# expansion_module_audio_line_out.net
KiCad netlist of a schematic drawn in EAGLE
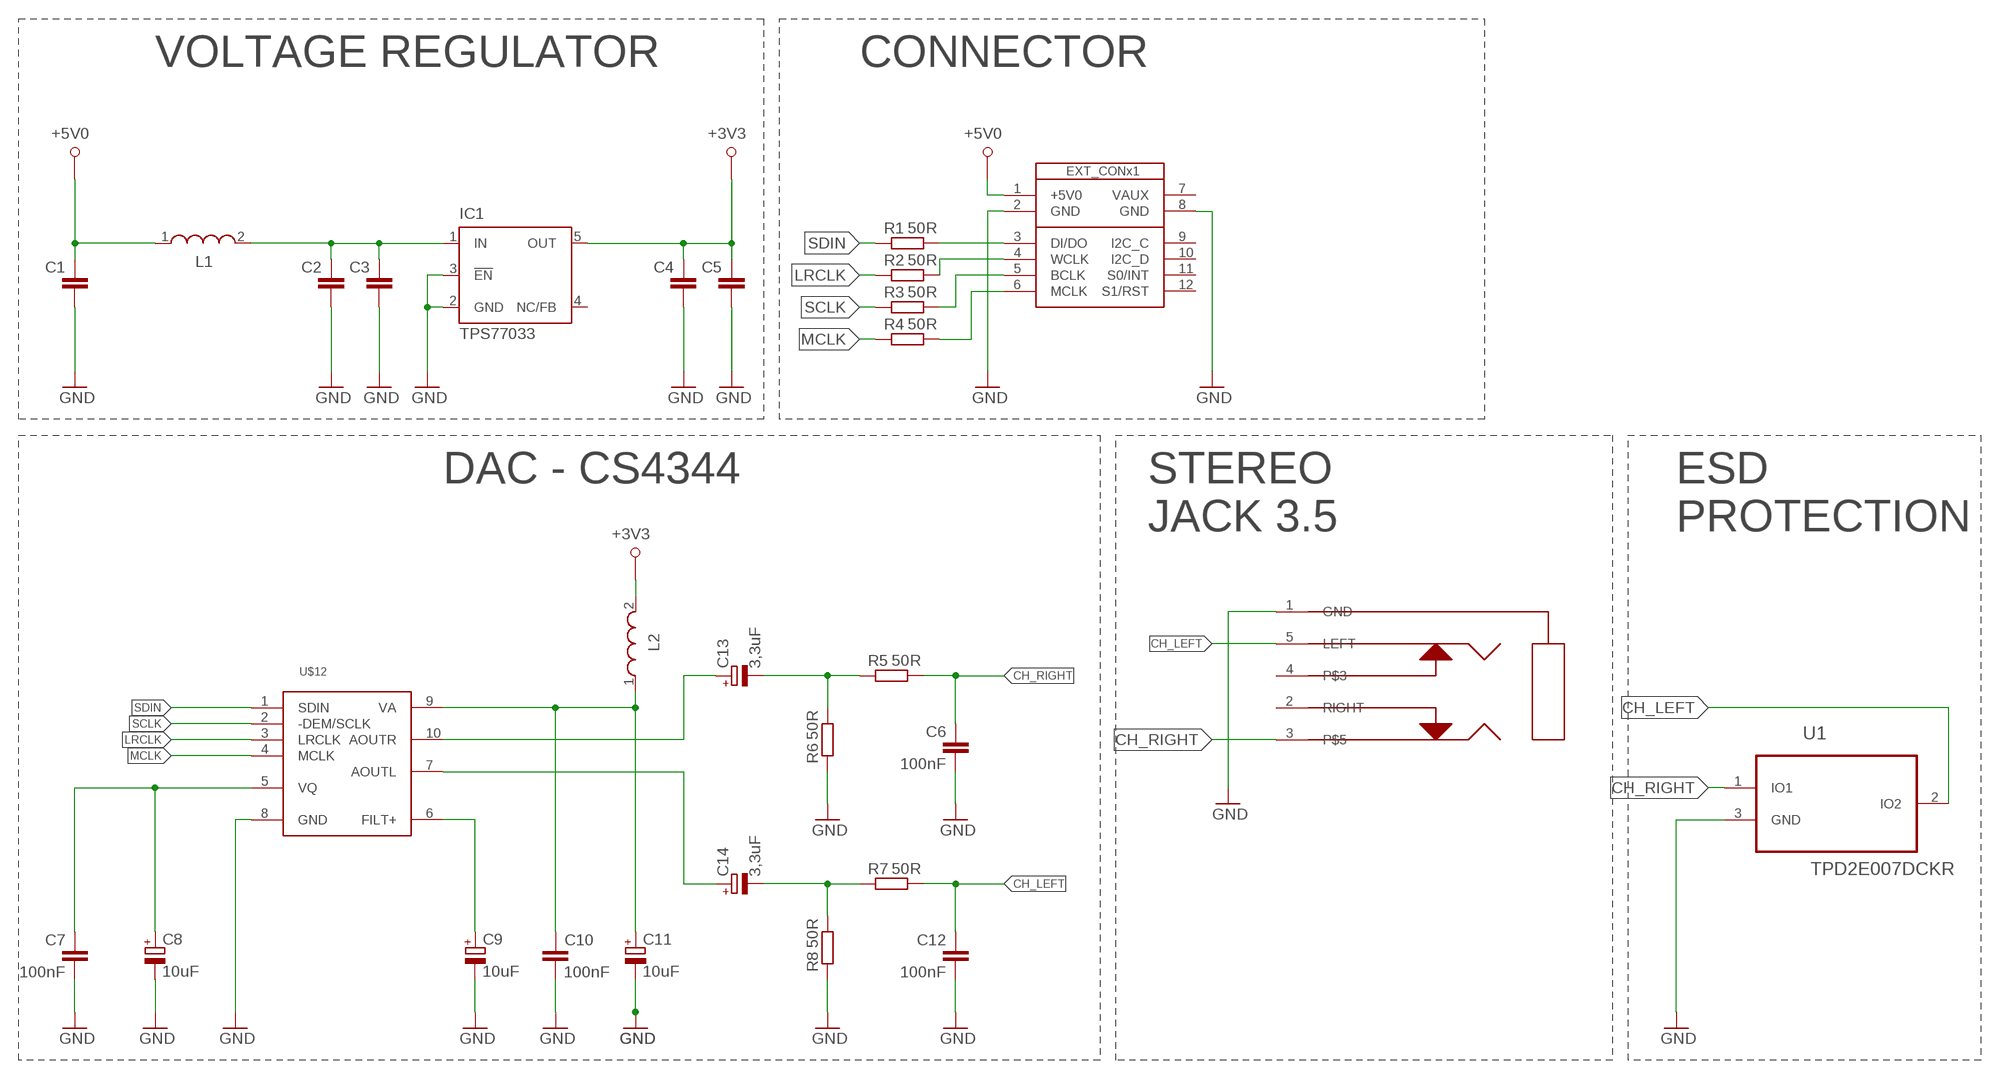
[diagram p0: schematic, sheet 1]

(export (version "E")
  (design (tool "Eeschema 10.0.6"))
  (components
    (comp (ref "C1")
      (value "C-EUC0805")
      (footprint "eagle-import:C0805")
      (libsource (lib "eagle-import") (part "C-EUC0805"))
    )
    (comp (ref "C2")
      (value "C-EUC0805")
      (footprint "eagle-import:C0805")
      (libsource (lib "eagle-import") (part "C-EUC0805"))
    )
    (comp (ref "C3")
      (value "C-EUC0805")
      (footprint "eagle-import:C0805")
      (libsource (lib "eagle-import") (part "C-EUC0805"))
    )
    (comp (ref "C4")
      (value "C-EUC0805")
      (footprint "eagle-import:C0805")
      (libsource (lib "eagle-import") (part "C-EUC0805"))
    )
    (comp (ref "C5")
      (value "C-EUC0805")
      (footprint "eagle-import:C0805")
      (libsource (lib "eagle-import") (part "C-EUC0805"))
    )
    (comp (ref "C6")
      (value "100nF")
      (footprint "eagle-import:C0805")
      (libsource (lib "eagle-import") (part "C-EUC0805"))
    )
    (comp (ref "C7")
      (value "100nF")
      (footprint "eagle-import:C0805")
      (libsource (lib "eagle-import") (part "C-EUC0805"))
    )
    (comp (ref "C8")
      (value "10uF")
      (footprint "eagle-import:SMC_A")
      (libsource (lib "eagle-import") (part "CPOL-EUSMCA"))
    )
    (comp (ref "C9")
      (value "10uF")
      (footprint "eagle-import:SMC_A")
      (libsource (lib "eagle-import") (part "CPOL-EUSMCA"))
    )
    (comp (ref "C10")
      (value "100nF")
      (footprint "eagle-import:C0805")
      (libsource (lib "eagle-import") (part "C-EUC0805"))
    )
    (comp (ref "C11")
      (value "10uF")
      (footprint "eagle-import:SMC_A")
      (libsource (lib "eagle-import") (part "CPOL-EUSMCA"))
    )
    (comp (ref "C12")
      (value "100nF")
      (footprint "eagle-import:C0805")
      (libsource (lib "eagle-import") (part "C-EUC0805"))
    )
    (comp (ref "C13")
      (value "3,3uF")
      (footprint "eagle-import:SMC_A")
      (libsource (lib "eagle-import") (part "CPOL-EUSMCA"))
    )
    (comp (ref "C14")
      (value "3,3uF")
      (footprint "eagle-import:SMC_A")
      (libsource (lib "eagle-import") (part "CPOL-EUSMCA"))
    )
    (comp (ref "IC1")
      (value "TPS77033")
      (footprint "eagle-import:SOT23-DBV")
      (fields (field (name "MF") "TEXAS INSTRUMENTS") (field (name "MPN") "TPS77033DBVT"))
      (libsource (lib "eagle-import") (part "TPS77033"))
    )
    (comp (ref "L1")
      (value "WE-LQ_1210")
      (footprint "eagle-import:WE-LQ_M")
      (libsource (lib "eagle-import") (part "WE-LQ_1210"))
    )
    (comp (ref "L2")
      (value "WE-LQ_1210")
      (footprint "eagle-import:WE-LQ_M")
      (libsource (lib "eagle-import") (part "WE-LQ_1210"))
    )
    (comp (ref "R1")
      (value "50R")
      (footprint "eagle-import:R0805")
      (libsource (lib "eagle-import") (part "R-EU_R0805"))
    )
    (comp (ref "R2")
      (value "50R")
      (footprint "eagle-import:R0805")
      (libsource (lib "eagle-import") (part "R-EU_R0805"))
    )
    (comp (ref "R3")
      (value "50R")
      (footprint "eagle-import:R0805")
      (libsource (lib "eagle-import") (part "R-EU_R0805"))
    )
    (comp (ref "R4")
      (value "50R")
      (footprint "eagle-import:R0805")
      (libsource (lib "eagle-import") (part "R-EU_R0805"))
    )
    (comp (ref "R5")
      (value "50R")
      (footprint "eagle-import:R0805")
      (libsource (lib "eagle-import") (part "R-EU_R0805"))
    )
    (comp (ref "R6")
      (value "50R")
      (footprint "eagle-import:R0805")
      (libsource (lib "eagle-import") (part "R-EU_R0805"))
    )
    (comp (ref "R7")
      (value "50R")
      (footprint "eagle-import:R0805")
      (libsource (lib "eagle-import") (part "R-EU_R0805"))
    )
    (comp (ref "R8")
      (value "50R")
      (footprint "eagle-import:R0805")
      (libsource (lib "eagle-import") (part "R-EU_R0805"))
    )
    (comp (ref "U$1")
      (value "SB_EXT_CON_X1_I2S")
      (footprint "eagle-import:SB_EXT_CON_X1_FULL")
      (libsource (lib "eagle-import") (part "SB_EXT_CON_X1_I2S"))
    )
    (comp (ref "U$12")
      (value "CS4344")
      (footprint "eagle-import:MSOP10")
      (libsource (lib "eagle-import") (part "CS4344"))
    )
    (comp (ref "U$27")
      (value "JACK_STEREO_5_PIN")
      (footprint "eagle-import:JACK_STEREO_5_PIN")
      (libsource (lib "eagle-import") (part "JACK_STEREO_5_PIN"))
    )
    (comp (ref "U1")
      (value "TPD2E007DCKR")
      (footprint "eagle-import:SOT65P210X110-3N")
      (libsource (lib "eagle-import") (part "TPD2E007DCKR"))
    )
  )
  (nets
    (net (code "1") (name "+3V3") (class "Default")
      (node (ref "C4") (pin "2") (pinfunction "2_2") (pintype "passive"))
      (node (ref "C5") (pin "2") (pinfunction "2_2") (pintype "passive"))
      (node (ref "IC1") (pin "5") (pinfunction "OUT_5") (pintype "passive"))
      (node (ref "L2") (pin "2") (pinfunction "2_2") (pintype "passive"))
    )
    (net (code "2") (name "+5V0") (class "Default")
      (node (ref "C1") (pin "2") (pinfunction "2_2") (pintype "passive"))
      (node (ref "L1") (pin "1") (pinfunction "1_1") (pintype "passive"))
      (node (ref "U$1") (pin "1") (pinfunction "+5V0_1") (pintype "bidirectional"))
    )
    (net (code "3") (name "CH_LEFT") (class "Default")
      (node (ref "C12") (pin "2") (pinfunction "2_2") (pintype "passive"))
      (node (ref "R7") (pin "2") (pinfunction "2_2") (pintype "passive"))
      (node (ref "U$27") (pin "5") (pinfunction "LEFT_5") (pintype "bidirectional"))
      (node (ref "U1") (pin "2") (pinfunction "IO2_2") (pintype "bidirectional"))
    )
    (net (code "4") (name "CH_RIGHT") (class "Default")
      (node (ref "C6") (pin "2") (pinfunction "2_2") (pintype "passive"))
      (node (ref "R5") (pin "2") (pinfunction "2_2") (pintype "passive"))
      (node (ref "U$27") (pin "3") (pinfunction "P$5_3") (pintype "bidirectional"))
      (node (ref "U1") (pin "1") (pinfunction "IO1_1") (pintype "bidirectional"))
    )
    (net (code "5") (name "GND") (class "Default")
      (node (ref "C1") (pin "1") (pinfunction "1_1") (pintype "passive"))
      (node (ref "C10") (pin "1") (pinfunction "1_1") (pintype "passive"))
      (node (ref "C11") (pin "-") (pinfunction "-_-") (pintype "passive"))
      (node (ref "C12") (pin "1") (pinfunction "1_1") (pintype "passive"))
      (node (ref "C2") (pin "1") (pinfunction "1_1") (pintype "passive"))
      (node (ref "C3") (pin "1") (pinfunction "1_1") (pintype "passive"))
      (node (ref "C4") (pin "1") (pinfunction "1_1") (pintype "passive"))
      (node (ref "C5") (pin "1") (pinfunction "1_1") (pintype "passive"))
      (node (ref "C6") (pin "1") (pinfunction "1_1") (pintype "passive"))
      (node (ref "C7") (pin "1") (pinfunction "1_1") (pintype "passive"))
      (node (ref "C8") (pin "-") (pinfunction "-_-") (pintype "passive"))
      (node (ref "C9") (pin "-") (pinfunction "-_-") (pintype "passive"))
      (node (ref "IC1") (pin "2") (pinfunction "GND_2") (pintype "power_in"))
      (node (ref "IC1") (pin "3") (pinfunction "~{EN}_3") (pintype "input"))
      (node (ref "R6") (pin "1") (pinfunction "1_1") (pintype "passive"))
      (node (ref "R8") (pin "1") (pinfunction "1_1") (pintype "passive"))
      (node (ref "U$1") (pin "2") (pinfunction "GND_2") (pintype "bidirectional"))
      (node (ref "U$1") (pin "8") (pinfunction "GND_8") (pintype "bidirectional"))
      (node (ref "U$12") (pin "8") (pinfunction "GND_8") (pintype "power_in"))
      (node (ref "U$27") (pin "1") (pinfunction "GND_1") (pintype "bidirectional"))
      (node (ref "U1") (pin "3") (pinfunction "GND_3") (pintype "passive"))
    )
    (net (code "6") (name "LRCLK") (class "Default")
      (node (ref "R2") (pin "1") (pinfunction "1_1") (pintype "passive"))
      (node (ref "U$12") (pin "3") (pinfunction "LRCLK_3") (pintype "input"))
    )
    (net (code "7") (name "MCLK") (class "Default")
      (node (ref "R4") (pin "1") (pinfunction "1_1") (pintype "passive"))
      (node (ref "U$12") (pin "4") (pinfunction "MCLK_4") (pintype "input"))
    )
    (net (code "8") (name "Net-(C13-Pad-)") (class "Default")
      (node (ref "C13") (pin "-") (pinfunction "-_-") (pintype "passive"))
      (node (ref "R5") (pin "1") (pinfunction "1_1") (pintype "passive"))
      (node (ref "R6") (pin "2") (pinfunction "2_2") (pintype "passive"))
    )
    (net (code "9") (name "Net-(C14-Pad-)") (class "Default")
      (node (ref "C14") (pin "-") (pinfunction "-_-") (pintype "passive"))
      (node (ref "R7") (pin "1") (pinfunction "1_1") (pintype "passive"))
      (node (ref "R8") (pin "2") (pinfunction "2_2") (pintype "passive"))
    )
    (net (code "10") (name "Net-(IC1-IN)") (class "Default")
      (node (ref "C2") (pin "2") (pinfunction "2_2") (pintype "passive"))
      (node (ref "C3") (pin "2") (pinfunction "2_2") (pintype "passive"))
      (node (ref "IC1") (pin "1") (pinfunction "IN_1") (pintype "input"))
      (node (ref "L1") (pin "2") (pinfunction "2_2") (pintype "passive"))
    )
    (net (code "11") (name "Net-(U$1-BCLK)") (class "Default")
      (node (ref "R3") (pin "2") (pinfunction "2_2") (pintype "passive"))
      (node (ref "U$1") (pin "5") (pinfunction "BCLK_5") (pintype "bidirectional"))
    )
    (net (code "12") (name "Net-(U$1-DI{slash}DO)") (class "Default")
      (node (ref "R1") (pin "2") (pinfunction "2_2") (pintype "passive"))
      (node (ref "U$1") (pin "3") (pinfunction "DI/DO_3") (pintype "bidirectional"))
    )
    (net (code "13") (name "Net-(U$1-MCLK)") (class "Default")
      (node (ref "R4") (pin "2") (pinfunction "2_2") (pintype "passive"))
      (node (ref "U$1") (pin "6") (pinfunction "MCLK_6") (pintype "bidirectional"))
    )
    (net (code "14") (name "Net-(U$1-WCLK)") (class "Default")
      (node (ref "R2") (pin "2") (pinfunction "2_2") (pintype "passive"))
      (node (ref "U$1") (pin "4") (pinfunction "WCLK_4") (pintype "bidirectional"))
    )
    (net (code "15") (name "Net-(U$12-AOUTL)") (class "Default")
      (node (ref "C14") (pin "+") (pinfunction "+_+") (pintype "passive"))
      (node (ref "U$12") (pin "7") (pinfunction "AOUTL_7") (pintype "output"))
    )
    (net (code "16") (name "Net-(U$12-AOUTR)") (class "Default")
      (node (ref "C13") (pin "+") (pinfunction "+_+") (pintype "passive"))
      (node (ref "U$12") (pin "10") (pinfunction "AOUTR_10") (pintype "output"))
    )
    (net (code "17") (name "Net-(U$12-FILT+)") (class "Default")
      (node (ref "C9") (pin "+") (pinfunction "+_+") (pintype "passive"))
      (node (ref "U$12") (pin "6") (pinfunction "FILT+_6") (pintype "passive"))
    )
    (net (code "18") (name "Net-(U$12-VA)") (class "Default")
      (node (ref "C10") (pin "2") (pinfunction "2_2") (pintype "passive"))
      (node (ref "C11") (pin "+") (pinfunction "+_+") (pintype "passive"))
      (node (ref "L2") (pin "1") (pinfunction "1_1") (pintype "passive"))
      (node (ref "U$12") (pin "9") (pinfunction "VA_9") (pintype "power_in"))
    )
    (net (code "19") (name "Net-(U$12-VQ)") (class "Default")
      (node (ref "C7") (pin "2") (pinfunction "2_2") (pintype "passive"))
      (node (ref "C8") (pin "+") (pinfunction "+_+") (pintype "passive"))
      (node (ref "U$12") (pin "5") (pinfunction "VQ_5") (pintype "passive"))
    )
    (net (code "20") (name "SCLK") (class "Default")
      (node (ref "R3") (pin "1") (pinfunction "1_1") (pintype "passive"))
      (node (ref "U$12") (pin "2") (pinfunction "-DEM/SCLK_2") (pintype "input"))
    )
    (net (code "21") (name "SDIN") (class "Default")
      (node (ref "R1") (pin "1") (pinfunction "1_1") (pintype "passive"))
      (node (ref "U$12") (pin "1") (pinfunction "SDIN_1") (pintype "input"))
    )
    (net (code "22") (name "unconnected-(IC1-NC{slash}FB-Pad4)") (class "Default")
      (node (ref "IC1") (pin "4") (pinfunction "NC/FB_4") (pintype "passive"))
    )
    (net (code "23") (name "unconnected-(U$1-I2C_C-Pad9)") (class "Default")
      (node (ref "U$1") (pin "9") (pinfunction "I2C_C_9") (pintype "bidirectional"))
    )
    (net (code "24") (name "unconnected-(U$1-I2C_D-Pad10)") (class "Default")
      (node (ref "U$1") (pin "10") (pinfunction "I2C_D_10") (pintype "bidirectional"))
    )
    (net (code "25") (name "unconnected-(U$1-S0{slash}INT-Pad11)") (class "Default")
      (node (ref "U$1") (pin "11") (pinfunction "S0/INT_11") (pintype "bidirectional"))
    )
    (net (code "26") (name "unconnected-(U$1-S1{slash}RST-Pad12)") (class "Default")
      (node (ref "U$1") (pin "12") (pinfunction "S1/RST_12") (pintype "bidirectional"))
    )
    (net (code "27") (name "unconnected-(U$1-VAUX-Pad7)") (class "Default")
      (node (ref "U$1") (pin "7") (pinfunction "VAUX_7") (pintype "bidirectional"))
    )
    (net (code "28") (name "unconnected-(U$27-P$3-Pad4)") (class "Default")
      (node (ref "U$27") (pin "4") (pinfunction "P$3_4") (pintype "bidirectional"))
    )
    (net (code "29") (name "unconnected-(U$27-RIGHT-Pad2)") (class "Default")
      (node (ref "U$27") (pin "2") (pinfunction "RIGHT_2") (pintype "bidirectional"))
    )
  )
)
